# optoiso.net
KiCad netlist of a schematic drawn in Altium Designer
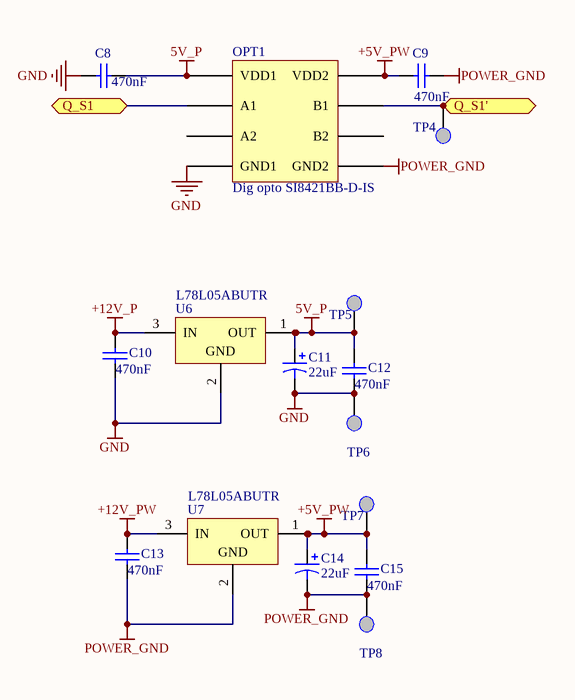
[diagram p0: optoiso.SchDoc]

(export (version "E")
  (design (tool "Eeschema 10.0.6"))
  (components
    (comp (ref "C8")
      (value "470nF")
      (footprint "Capacitor 0805")
      (description "Capacitor")
      (fields (field (name "Comment") "Cap") (field (name "PUBLISHER") "Altium Limited"))
      (libsource (lib "Miscellaneous Devices") (part "Cap"))
    )
    (comp (ref "C9")
      (value "470nF")
      (footprint "Capacitor 0805")
      (description "Capacitor")
      (fields (field (name "Comment") "Cap") (field (name "PUBLISHER") "Altium Limited"))
      (libsource (lib "Miscellaneous Devices") (part "Cap"))
    )
    (comp (ref "C10")
      (value "470nF")
      (footprint "Capacitor 0805")
      (description "Capacitor")
      (fields (field (name "Comment") "Cap") (field (name "PUBLISHER") "Altium Limited"))
      (libsource (lib "Miscellaneous Devices") (part "Cap"))
    )
    (comp (ref "C11")
      (value "22uF")
      (footprint "Cap Tantal 3216")
      (description "Polarized Capacitor (Radial)")
      (fields
        (field (name "Comment") "Tantalium/T520A226M006ATE090")
        (field (name "PUBLISHER") "Altium Limited")
      )
      (libsource (lib "Miscellaneous Devices") (part "Cap Pol1"))
    )
    (comp (ref "C12")
      (value "470nF")
      (footprint "Capacitor 0805")
      (description "Capacitor")
      (fields (field (name "Comment") "Cap") (field (name "PUBLISHER") "Altium Limited"))
      (libsource (lib "Miscellaneous Devices") (part "Cap"))
    )
    (comp (ref "C13")
      (value "470nF")
      (footprint "Capacitor 0805")
      (description "Capacitor")
      (fields (field (name "Comment") "Cap") (field (name "PUBLISHER") "Altium Limited"))
      (libsource (lib "Miscellaneous Devices") (part "Cap"))
    )
    (comp (ref "C14")
      (value "22uF")
      (footprint "Cap Tantal 3216")
      (description "Polarized Capacitor (Radial)")
      (fields
        (field (name "Comment") "Tantalium/T520A226M006ATE090")
        (field (name "PUBLISHER") "Altium Limited")
      )
      (libsource (lib "Miscellaneous Devices") (part "Cap Pol1"))
    )
    (comp (ref "C15")
      (value "470nF")
      (footprint "Capacitor 0805")
      (description "Capacitor")
      (fields (field (name "Comment") "Cap") (field (name "PUBLISHER") "Altium Limited"))
      (libsource (lib "Miscellaneous Devices") (part "Cap"))
    )
    (comp (ref "OPT1")
      (value "Dig opto SI8421BB-D-IS")
      (footprint "SO8 TS27l2")
      (libsource (lib "si8421") (part "Component_1"))
    )
    (comp (ref "TP4")
      (value "Test point")
      (footprint "Test Point")
      (libsource (lib "CUK1") (part "Test point"))
    )
    (comp (ref "TP5")
      (value "Test point")
      (footprint "Test Point")
      (libsource (lib "CUK1") (part "Test point"))
    )
    (comp (ref "TP6")
      (value "Test point")
      (footprint "Test Point")
      (libsource (lib "CUK1") (part "Test point"))
    )
    (comp (ref "TP7")
      (value "Test point")
      (footprint "Test Point")
      (libsource (lib "CUK1") (part "Test point"))
    )
    (comp (ref "TP8")
      (value "Test point")
      (footprint "Test Point")
      (libsource (lib "CUK1") (part "Test point"))
    )
    (comp (ref "U6")
      (value "L78L05ABUTR")
      (footprint "Reg SOT-89 +5")
      (description "Positive Voltage Regulator")
      (fields (field (name "PUBLISHER") "Altium Limited"))
      (libsource (lib "ST Power Mgt Voltage Regulator") (part "L78L05ABZ"))
    )
    (comp (ref "U7")
      (value "L78L05ABUTR")
      (footprint "Reg SOT-89 +5")
      (description "Positive Voltage Regulator")
      (fields (field (name "PUBLISHER") "Altium Limited"))
      (libsource (lib "ST Power Mgt Voltage Regulator") (part "L78L05ABZ"))
    )
  )
  (nets
    (net (code "1") (name "+5V_PW") (class "Default")
      (node (ref "C14") (pin "1") (pinfunction "1_1") (pintype "passive"))
      (node (ref "C15") (pin "2") (pinfunction "2_2") (pintype "passive"))
      (node (ref "C9") (pin "1") (pinfunction "1_1") (pintype "passive"))
      (node (ref "OPT1") (pin "8") (pinfunction "VDD2_8") (pintype "passive"))
      (node (ref "TP7") (pin "1") (pintype "passive"))
      (node (ref "U7") (pin "1") (pinfunction "OUT_1") (pintype "power_in"))
    )
    (net (code "2") (name "+12V_P") (class "Default")
      (node (ref "C10") (pin "2") (pinfunction "2_2") (pintype "passive"))
      (node (ref "U6") (pin "3") (pinfunction "IN_3") (pintype "power_in"))
    )
    (net (code "3") (name "+12V_PW") (class "Default")
      (node (ref "C13") (pin "2") (pinfunction "2_2") (pintype "passive"))
      (node (ref "U7") (pin "3") (pinfunction "IN_3") (pintype "power_in"))
    )
    (net (code "4") (name "/Q_S1") (class "Default")
      (node (ref "OPT1") (pin "2") (pinfunction "A1_2") (pintype "passive"))
    )
    (net (code "5") (name "/Q_S1'") (class "Default")
      (node (ref "OPT1") (pin "7") (pinfunction "B1_7") (pintype "passive"))
      (node (ref "TP4") (pin "1") (pintype "passive"))
    )
    (net (code "6") (name "5V_P") (class "Default")
      (node (ref "C11") (pin "1") (pinfunction "1_1") (pintype "passive"))
      (node (ref "C12") (pin "2") (pinfunction "2_2") (pintype "passive"))
      (node (ref "C8") (pin "1") (pinfunction "1_1") (pintype "passive"))
      (node (ref "OPT1") (pin "1") (pinfunction "VDD1_1") (pintype "passive"))
      (node (ref "TP5") (pin "1") (pintype "passive"))
      (node (ref "U6") (pin "1") (pinfunction "OUT_1") (pintype "power_in"))
    )
    (net (code "7") (name "GND") (class "Default")
      (node (ref "C10") (pin "1") (pinfunction "1_1") (pintype "passive"))
      (node (ref "C11") (pin "2") (pinfunction "2_2") (pintype "passive"))
      (node (ref "C12") (pin "1") (pinfunction "1_1") (pintype "passive"))
      (node (ref "C8") (pin "2") (pinfunction "2_2") (pintype "passive"))
      (node (ref "OPT1") (pin "4") (pinfunction "GND1_4") (pintype "passive"))
      (node (ref "TP6") (pin "1") (pintype "passive"))
      (node (ref "U6") (pin "2") (pinfunction "GND_2") (pintype "power_in"))
    )
    (net (code "8") (name "POWER_GND") (class "Default")
      (node (ref "C13") (pin "1") (pinfunction "1_1") (pintype "passive"))
      (node (ref "C14") (pin "2") (pinfunction "2_2") (pintype "passive"))
      (node (ref "C15") (pin "1") (pinfunction "1_1") (pintype "passive"))
      (node (ref "C9") (pin "2") (pinfunction "2_2") (pintype "passive"))
      (node (ref "OPT1") (pin "5") (pinfunction "GND2_5") (pintype "passive"))
      (node (ref "TP8") (pin "1") (pintype "passive"))
      (node (ref "U7") (pin "2") (pinfunction "GND_2") (pintype "power_in"))
    )
    (net (code "9") (name "unconnected-(OPT1-A2-Pad3)") (class "Default")
      (node (ref "OPT1") (pin "3") (pinfunction "A2_3") (pintype "passive"))
    )
    (net (code "10") (name "unconnected-(OPT1-B2-Pad6)") (class "Default")
      (node (ref "OPT1") (pin "6") (pinfunction "B2_6") (pintype "passive"))
    )
  )
)
